# servo-connector.net
KiCad netlist of a schematic drawn in Altium Designer
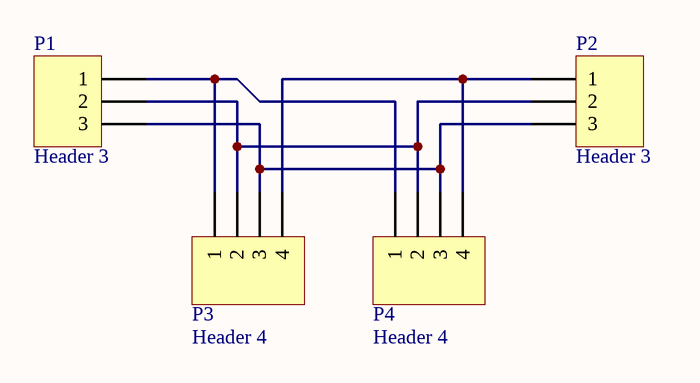
[diagram p0: servo-connector.SchDoc]

(export (version "E")
  (design (tool "Eeschema 10.0.6"))
  (components
    (comp (ref "P1")
      (value "Header 3")
      (footprint "HDR1X3")
      (description "Header, 3-Pin")
      (fields (field (name "PUBLISHER") "Altium Limited"))
      (libsource (lib "") (part "Header 3_1"))
    )
    (comp (ref "P2")
      (value "Header 3")
      (footprint "HDR1X3")
      (description "Header, 3-Pin")
      (fields (field (name "PUBLISHER") "Altium Limited"))
      (libsource (lib "Miscellaneous Connectors") (part "Header 3"))
    )
    (comp (ref "P3")
      (value "Header 4")
      (footprint "HDR1X4")
      (description "Header, 4-Pin")
      (fields (field (name "PUBLISHER") "Altium Limited"))
      (libsource (lib "Miscellaneous Connectors") (part "Header 4"))
    )
    (comp (ref "P4")
      (value "Header 4")
      (footprint "HDR1X4")
      (description "Header, 4-Pin")
      (fields (field (name "PUBLISHER") "Altium Limited"))
      (libsource (lib "Miscellaneous Connectors") (part "Header 4"))
    )
  )
  (nets
    (net (code "1") (name "Net-(P1-Pad1)") (class "Default")
      (node (ref "P1") (pin "1") (pinfunction "1_1") (pintype "passive"))
      (node (ref "P3") (pin "1") (pinfunction "1_1") (pintype "passive"))
      (node (ref "P4") (pin "1") (pinfunction "1_1") (pintype "passive"))
    )
    (net (code "2") (name "Net-(P1-Pad2)") (class "Default")
      (node (ref "P1") (pin "2") (pinfunction "2_2") (pintype "passive"))
      (node (ref "P2") (pin "2") (pinfunction "2_2") (pintype "passive"))
      (node (ref "P3") (pin "2") (pinfunction "2_2") (pintype "passive"))
      (node (ref "P4") (pin "2") (pinfunction "2_2") (pintype "passive"))
    )
    (net (code "3") (name "Net-(P1-Pad3)") (class "Default")
      (node (ref "P1") (pin "3") (pinfunction "3_3") (pintype "passive"))
      (node (ref "P2") (pin "3") (pinfunction "3_3") (pintype "passive"))
      (node (ref "P3") (pin "3") (pinfunction "3_3") (pintype "passive"))
      (node (ref "P4") (pin "3") (pinfunction "3_3") (pintype "passive"))
    )
    (net (code "4") (name "Net-(P2-Pad1)") (class "Default")
      (node (ref "P2") (pin "1") (pinfunction "1_1") (pintype "passive"))
      (node (ref "P3") (pin "4") (pinfunction "4_4") (pintype "passive"))
      (node (ref "P4") (pin "4") (pinfunction "4_4") (pintype "passive"))
    )
  )
)
